# fightboard-tester.net
KiCad netlist of a schematic drawn in EAGLE
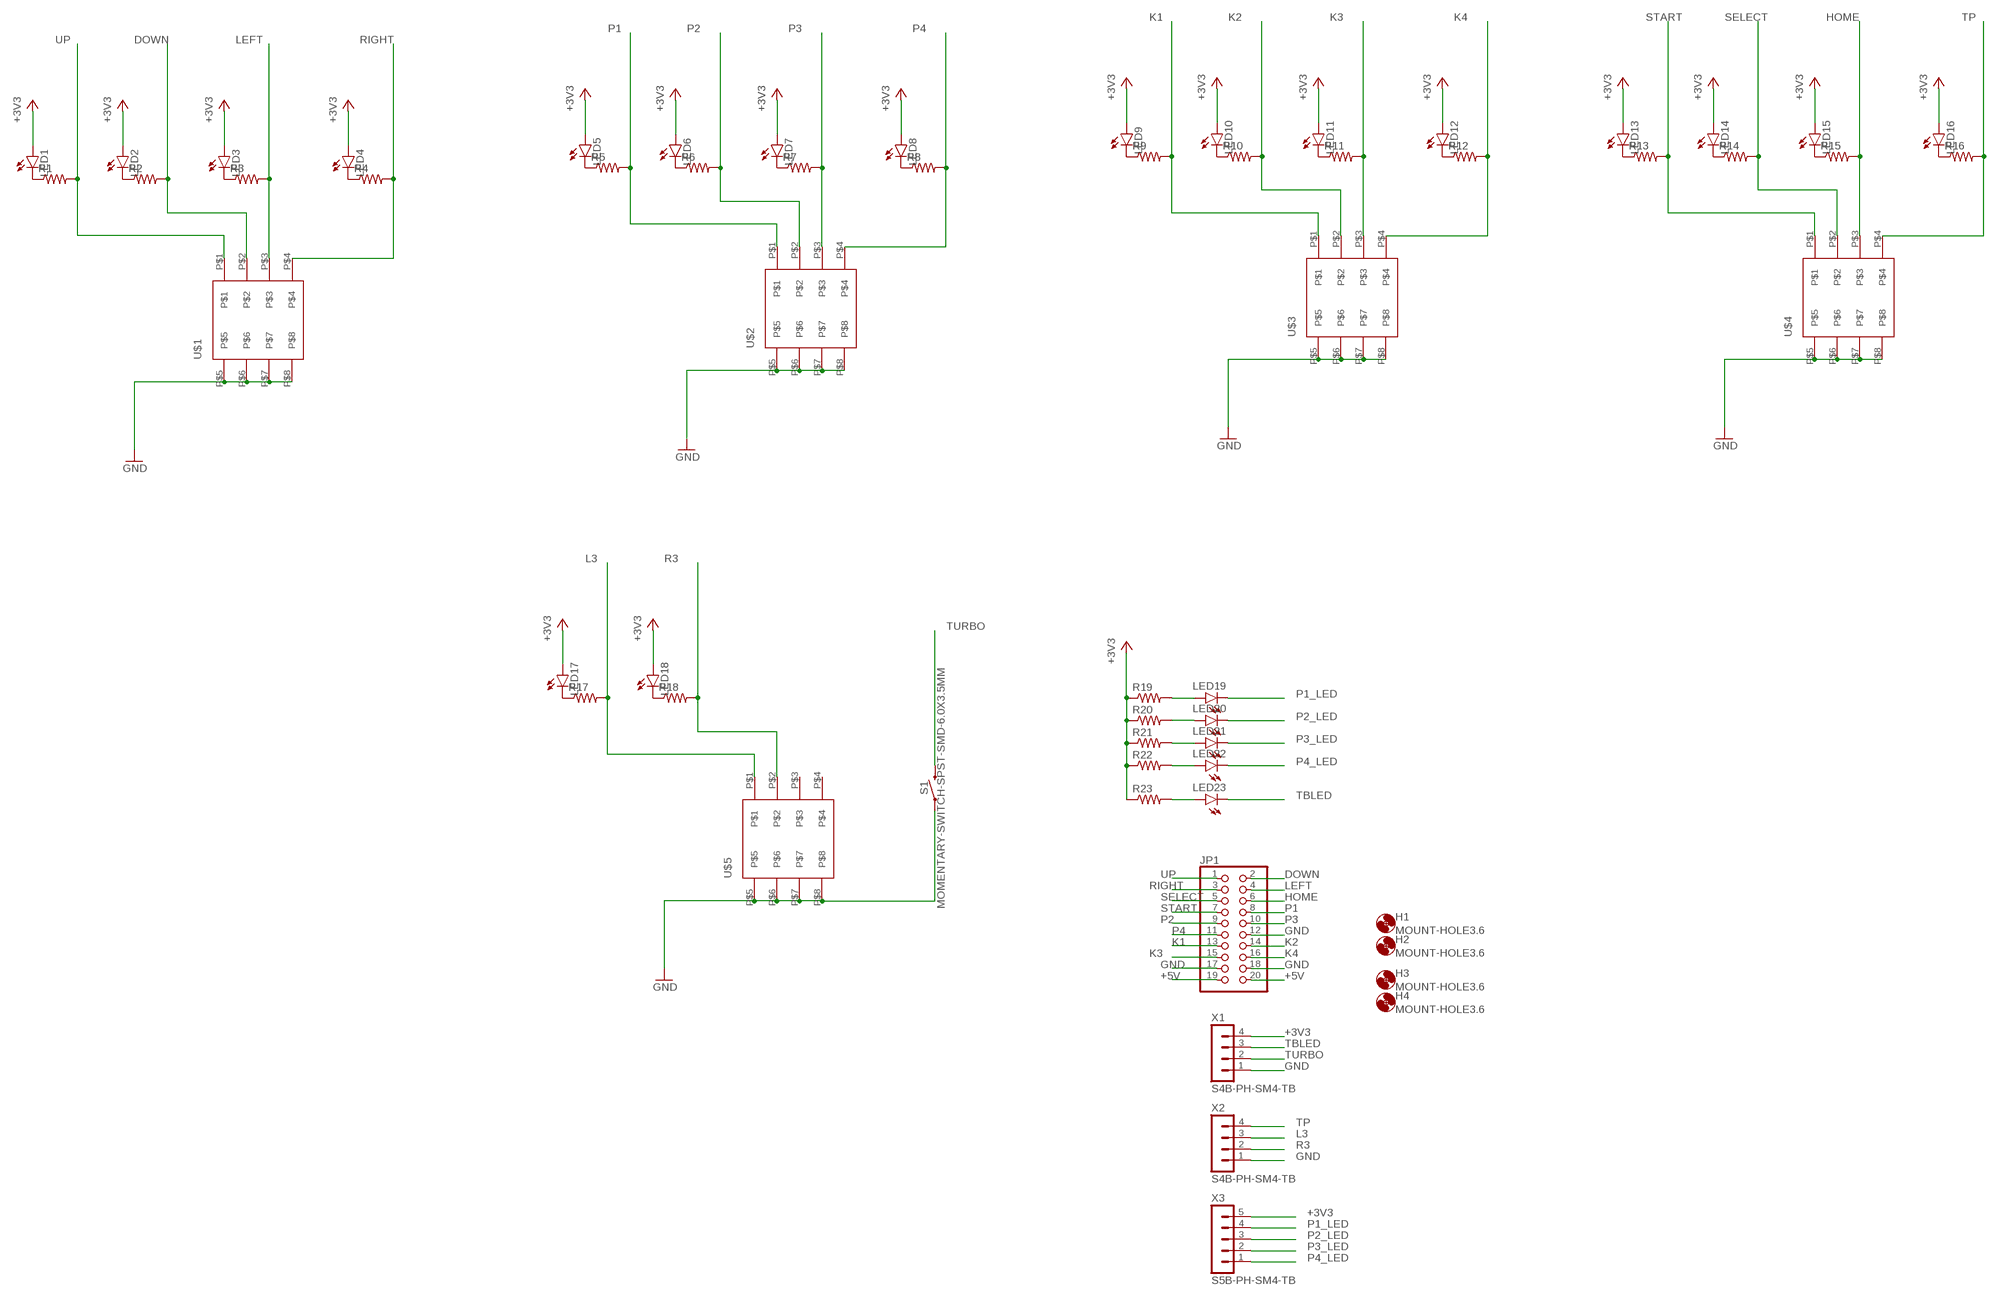
[diagram p0: schematic, sheet 1]

(export (version "E")
  (design (tool "Eeschema 10.0.6"))
  (components
    (comp (ref "H1")
      (value "MOUNT-HOLE3.6")
      (footprint "eagle-import:3,6")
      (libsource (lib "eagle-import") (part "MOUNT-HOLE3.6"))
    )
    (comp (ref "H2")
      (value "MOUNT-HOLE3.6")
      (footprint "eagle-import:3,6")
      (libsource (lib "eagle-import") (part "MOUNT-HOLE3.6"))
    )
    (comp (ref "H3")
      (value "MOUNT-HOLE3.6")
      (footprint "eagle-import:3,6")
      (libsource (lib "eagle-import") (part "MOUNT-HOLE3.6"))
    )
    (comp (ref "H4")
      (value "MOUNT-HOLE3.6")
      (footprint "eagle-import:3,6")
      (libsource (lib "eagle-import") (part "MOUNT-HOLE3.6"))
    )
    (comp (ref "JP1")
      (value "PINHD-2X10")
      (footprint "eagle-import:2X10")
      (libsource (lib "eagle-import") (part "PINHD-2X10"))
    )
    (comp (ref "LED1")
      (value "LEDCHIPLED_0805")
      (footprint "eagle-import:CHIPLED_0805")
      (libsource (lib "eagle-import") (part "LEDCHIPLED_0805"))
    )
    (comp (ref "LED2")
      (value "LEDCHIPLED_0805")
      (footprint "eagle-import:CHIPLED_0805")
      (libsource (lib "eagle-import") (part "LEDCHIPLED_0805"))
    )
    (comp (ref "LED3")
      (value "LEDCHIPLED_0805")
      (footprint "eagle-import:CHIPLED_0805")
      (libsource (lib "eagle-import") (part "LEDCHIPLED_0805"))
    )
    (comp (ref "LED4")
      (value "LEDCHIPLED_0805")
      (footprint "eagle-import:CHIPLED_0805")
      (libsource (lib "eagle-import") (part "LEDCHIPLED_0805"))
    )
    (comp (ref "LED5")
      (value "LEDCHIPLED_0805")
      (footprint "eagle-import:CHIPLED_0805")
      (libsource (lib "eagle-import") (part "LEDCHIPLED_0805"))
    )
    (comp (ref "LED6")
      (value "LEDCHIPLED_0805")
      (footprint "eagle-import:CHIPLED_0805")
      (libsource (lib "eagle-import") (part "LEDCHIPLED_0805"))
    )
    (comp (ref "LED7")
      (value "LEDCHIPLED_0805")
      (footprint "eagle-import:CHIPLED_0805")
      (libsource (lib "eagle-import") (part "LEDCHIPLED_0805"))
    )
    (comp (ref "LED8")
      (value "LEDCHIPLED_0805")
      (footprint "eagle-import:CHIPLED_0805")
      (libsource (lib "eagle-import") (part "LEDCHIPLED_0805"))
    )
    (comp (ref "LED9")
      (value "LEDCHIPLED_0805")
      (footprint "eagle-import:CHIPLED_0805")
      (libsource (lib "eagle-import") (part "LEDCHIPLED_0805"))
    )
    (comp (ref "LED10")
      (value "LEDCHIPLED_0805")
      (footprint "eagle-import:CHIPLED_0805")
      (libsource (lib "eagle-import") (part "LEDCHIPLED_0805"))
    )
    (comp (ref "LED11")
      (value "LEDCHIPLED_0805")
      (footprint "eagle-import:CHIPLED_0805")
      (libsource (lib "eagle-import") (part "LEDCHIPLED_0805"))
    )
    (comp (ref "LED12")
      (value "LEDCHIPLED_0805")
      (footprint "eagle-import:CHIPLED_0805")
      (libsource (lib "eagle-import") (part "LEDCHIPLED_0805"))
    )
    (comp (ref "LED13")
      (value "LEDCHIPLED_0805")
      (footprint "eagle-import:CHIPLED_0805")
      (libsource (lib "eagle-import") (part "LEDCHIPLED_0805"))
    )
    (comp (ref "LED14")
      (value "LEDCHIPLED_0805")
      (footprint "eagle-import:CHIPLED_0805")
      (libsource (lib "eagle-import") (part "LEDCHIPLED_0805"))
    )
    (comp (ref "LED15")
      (value "LEDCHIPLED_0805")
      (footprint "eagle-import:CHIPLED_0805")
      (libsource (lib "eagle-import") (part "LEDCHIPLED_0805"))
    )
    (comp (ref "LED16")
      (value "LEDCHIPLED_0805")
      (footprint "eagle-import:CHIPLED_0805")
      (libsource (lib "eagle-import") (part "LEDCHIPLED_0805"))
    )
    (comp (ref "LED17")
      (value "LEDCHIPLED_0805")
      (footprint "eagle-import:CHIPLED_0805")
      (libsource (lib "eagle-import") (part "LEDCHIPLED_0805"))
    )
    (comp (ref "LED18")
      (value "LEDCHIPLED_0805")
      (footprint "eagle-import:CHIPLED_0805")
      (libsource (lib "eagle-import") (part "LEDCHIPLED_0805"))
    )
    (comp (ref "LED19")
      (value "LEDCHIPLED_0805")
      (footprint "eagle-import:CHIPLED_0805")
      (libsource (lib "eagle-import") (part "LEDCHIPLED_0805"))
    )
    (comp (ref "LED20")
      (value "LEDCHIPLED_0805")
      (footprint "eagle-import:CHIPLED_0805")
      (libsource (lib "eagle-import") (part "LEDCHIPLED_0805"))
    )
    (comp (ref "LED21")
      (value "LEDCHIPLED_0805")
      (footprint "eagle-import:CHIPLED_0805")
      (libsource (lib "eagle-import") (part "LEDCHIPLED_0805"))
    )
    (comp (ref "LED22")
      (value "LEDCHIPLED_0805")
      (footprint "eagle-import:CHIPLED_0805")
      (libsource (lib "eagle-import") (part "LEDCHIPLED_0805"))
    )
    (comp (ref "LED23")
      (value "LEDCHIPLED_0805")
      (footprint "eagle-import:CHIPLED_0805")
      (libsource (lib "eagle-import") (part "LEDCHIPLED_0805"))
    )
    (comp (ref "R1")
      (value "R-US_R0805")
      (footprint "eagle-import:R0805")
      (libsource (lib "eagle-import") (part "R-US_R0805"))
    )
    (comp (ref "R2")
      (value "R-US_R0805")
      (footprint "eagle-import:R0805")
      (libsource (lib "eagle-import") (part "R-US_R0805"))
    )
    (comp (ref "R3")
      (value "R-US_R0805")
      (footprint "eagle-import:R0805")
      (libsource (lib "eagle-import") (part "R-US_R0805"))
    )
    (comp (ref "R4")
      (value "R-US_R0805")
      (footprint "eagle-import:R0805")
      (libsource (lib "eagle-import") (part "R-US_R0805"))
    )
    (comp (ref "R5")
      (value "R-US_R0805")
      (footprint "eagle-import:R0805")
      (libsource (lib "eagle-import") (part "R-US_R0805"))
    )
    (comp (ref "R6")
      (value "R-US_R0805")
      (footprint "eagle-import:R0805")
      (libsource (lib "eagle-import") (part "R-US_R0805"))
    )
    (comp (ref "R7")
      (value "R-US_R0805")
      (footprint "eagle-import:R0805")
      (libsource (lib "eagle-import") (part "R-US_R0805"))
    )
    (comp (ref "R8")
      (value "R-US_R0805")
      (footprint "eagle-import:R0805")
      (libsource (lib "eagle-import") (part "R-US_R0805"))
    )
    (comp (ref "R9")
      (value "R-US_R0805")
      (footprint "eagle-import:R0805")
      (libsource (lib "eagle-import") (part "R-US_R0805"))
    )
    (comp (ref "R10")
      (value "R-US_R0805")
      (footprint "eagle-import:R0805")
      (libsource (lib "eagle-import") (part "R-US_R0805"))
    )
    (comp (ref "R11")
      (value "R-US_R0805")
      (footprint "eagle-import:R0805")
      (libsource (lib "eagle-import") (part "R-US_R0805"))
    )
    (comp (ref "R12")
      (value "R-US_R0805")
      (footprint "eagle-import:R0805")
      (libsource (lib "eagle-import") (part "R-US_R0805"))
    )
    (comp (ref "R13")
      (value "R-US_R0805")
      (footprint "eagle-import:R0805")
      (libsource (lib "eagle-import") (part "R-US_R0805"))
    )
    (comp (ref "R14")
      (value "R-US_R0805")
      (footprint "eagle-import:R0805")
      (libsource (lib "eagle-import") (part "R-US_R0805"))
    )
    (comp (ref "R15")
      (value "R-US_R0805")
      (footprint "eagle-import:R0805")
      (libsource (lib "eagle-import") (part "R-US_R0805"))
    )
    (comp (ref "R16")
      (value "R-US_R0805")
      (footprint "eagle-import:R0805")
      (libsource (lib "eagle-import") (part "R-US_R0805"))
    )
    (comp (ref "R17")
      (value "R-US_R0805")
      (footprint "eagle-import:R0805")
      (libsource (lib "eagle-import") (part "R-US_R0805"))
    )
    (comp (ref "R18")
      (value "R-US_R0805")
      (footprint "eagle-import:R0805")
      (libsource (lib "eagle-import") (part "R-US_R0805"))
    )
    (comp (ref "R19")
      (value "R-US_R0805")
      (footprint "eagle-import:R0805")
      (libsource (lib "eagle-import") (part "R-US_R0805"))
    )
    (comp (ref "R20")
      (value "R-US_R0805")
      (footprint "eagle-import:R0805")
      (libsource (lib "eagle-import") (part "R-US_R0805"))
    )
    (comp (ref "R21")
      (value "R-US_R0805")
      (footprint "eagle-import:R0805")
      (libsource (lib "eagle-import") (part "R-US_R0805"))
    )
    (comp (ref "R22")
      (value "R-US_R0805")
      (footprint "eagle-import:R0805")
      (libsource (lib "eagle-import") (part "R-US_R0805"))
    )
    (comp (ref "R23")
      (value "R-US_R0805")
      (footprint "eagle-import:R0805")
      (libsource (lib "eagle-import") (part "R-US_R0805"))
    )
    (comp (ref "S1")
      (value "MOMENTARY-SWITCH-SPST-SMD-6.0X3.5MM")
      (footprint "eagle-import:TACTILE_SWITCH_SMD_6.0X3.5MM")
      (libsource (lib "eagle-import") (part "MOMENTARY-SWITCH-SPST-SMD-6.0X3.5MM"))
    )
    (comp (ref "U$1")
      (value "DSIC04LS")
      (footprint "eagle-import:DSIC04LS")
      (libsource (lib "eagle-import") (part "DSIC04LS"))
    )
    (comp (ref "U$2")
      (value "DSIC04LS")
      (footprint "eagle-import:DSIC04LS")
      (libsource (lib "eagle-import") (part "DSIC04LS"))
    )
    (comp (ref "U$3")
      (value "DSIC04LS")
      (footprint "eagle-import:DSIC04LS")
      (libsource (lib "eagle-import") (part "DSIC04LS"))
    )
    (comp (ref "U$4")
      (value "DSIC04LS")
      (footprint "eagle-import:DSIC04LS")
      (libsource (lib "eagle-import") (part "DSIC04LS"))
    )
    (comp (ref "U$5")
      (value "DSIC04LS")
      (footprint "eagle-import:DSIC04LS")
      (libsource (lib "eagle-import") (part "DSIC04LS"))
    )
    (comp (ref "X1")
      (value "S4B-PH-SM4-TB")
      (footprint "eagle-import:S4B-PH-SM4-TB")
      (libsource (lib "eagle-import") (part "S4B-PH-SM4-TB"))
    )
    (comp (ref "X2")
      (value "S4B-PH-SM4-TB")
      (footprint "eagle-import:S4B-PH-SM4-TB")
      (libsource (lib "eagle-import") (part "S4B-PH-SM4-TB"))
    )
    (comp (ref "X3")
      (value "S5B-PH-SM4-TB")
      (footprint "eagle-import:S5B-PH-SM4-TB")
      (libsource (lib "eagle-import") (part "S5B-PH-SM4-TB"))
    )
  )
  (nets
    (net (code "1") (name "+3V3") (class "Default")
      (node (ref "LED1") (pin "A") (pinfunction "A_A") (pintype "passive"))
      (node (ref "LED10") (pin "A") (pinfunction "A_A") (pintype "passive"))
      (node (ref "LED11") (pin "A") (pinfunction "A_A") (pintype "passive"))
      (node (ref "LED12") (pin "A") (pinfunction "A_A") (pintype "passive"))
      (node (ref "LED13") (pin "A") (pinfunction "A_A") (pintype "passive"))
      (node (ref "LED14") (pin "A") (pinfunction "A_A") (pintype "passive"))
      (node (ref "LED15") (pin "A") (pinfunction "A_A") (pintype "passive"))
      (node (ref "LED16") (pin "A") (pinfunction "A_A") (pintype "passive"))
      (node (ref "LED17") (pin "A") (pinfunction "A_A") (pintype "passive"))
      (node (ref "LED18") (pin "A") (pinfunction "A_A") (pintype "passive"))
      (node (ref "LED2") (pin "A") (pinfunction "A_A") (pintype "passive"))
      (node (ref "LED3") (pin "A") (pinfunction "A_A") (pintype "passive"))
      (node (ref "LED4") (pin "A") (pinfunction "A_A") (pintype "passive"))
      (node (ref "LED5") (pin "A") (pinfunction "A_A") (pintype "passive"))
      (node (ref "LED6") (pin "A") (pinfunction "A_A") (pintype "passive"))
      (node (ref "LED7") (pin "A") (pinfunction "A_A") (pintype "passive"))
      (node (ref "LED8") (pin "A") (pinfunction "A_A") (pintype "passive"))
      (node (ref "LED9") (pin "A") (pinfunction "A_A") (pintype "passive"))
      (node (ref "R19") (pin "1") (pinfunction "1_1") (pintype "passive"))
      (node (ref "R20") (pin "1") (pinfunction "1_1") (pintype "passive"))
      (node (ref "R21") (pin "1") (pinfunction "1_1") (pintype "passive"))
      (node (ref "R22") (pin "1") (pinfunction "1_1") (pintype "passive"))
      (node (ref "R23") (pin "1") (pinfunction "1_1") (pintype "passive"))
      (node (ref "X1") (pin "4") (pinfunction "4_4") (pintype "passive"))
      (node (ref "X3") (pin "5") (pinfunction "5_5") (pintype "passive"))
    )
    (net (code "2") (name "/+5V") (class "Default")
      (node (ref "JP1") (pin "19") (pinfunction "19_19") (pintype "passive"))
      (node (ref "JP1") (pin "20") (pinfunction "20_20") (pintype "passive"))
    )
    (net (code "3") (name "/DOWN") (class "Default")
      (node (ref "JP1") (pin "2") (pinfunction "2_2") (pintype "passive"))
      (node (ref "R2") (pin "2") (pinfunction "2_2") (pintype "passive"))
      (node (ref "U$1") (pin "P$2") (pinfunction "P$2_P$2") (pintype "bidirectional"))
    )
    (net (code "4") (name "/HOME") (class "Default")
      (node (ref "JP1") (pin "6") (pinfunction "6_6") (pintype "passive"))
      (node (ref "R15") (pin "2") (pinfunction "2_2") (pintype "passive"))
      (node (ref "U$4") (pin "P$3") (pinfunction "P$3_P$3") (pintype "bidirectional"))
    )
    (net (code "5") (name "/K1") (class "Default")
      (node (ref "JP1") (pin "13") (pinfunction "13_13") (pintype "passive"))
      (node (ref "R9") (pin "2") (pinfunction "2_2") (pintype "passive"))
      (node (ref "U$3") (pin "P$1") (pinfunction "P$1_P$1") (pintype "bidirectional"))
    )
    (net (code "6") (name "/K2") (class "Default")
      (node (ref "JP1") (pin "14") (pinfunction "14_14") (pintype "passive"))
      (node (ref "R10") (pin "2") (pinfunction "2_2") (pintype "passive"))
      (node (ref "U$3") (pin "P$2") (pinfunction "P$2_P$2") (pintype "bidirectional"))
    )
    (net (code "7") (name "/K3") (class "Default")
      (node (ref "JP1") (pin "15") (pinfunction "15_15") (pintype "passive"))
      (node (ref "R11") (pin "2") (pinfunction "2_2") (pintype "passive"))
      (node (ref "U$3") (pin "P$3") (pinfunction "P$3_P$3") (pintype "bidirectional"))
    )
    (net (code "8") (name "/K4") (class "Default")
      (node (ref "JP1") (pin "16") (pinfunction "16_16") (pintype "passive"))
      (node (ref "R12") (pin "2") (pinfunction "2_2") (pintype "passive"))
      (node (ref "U$3") (pin "P$4") (pinfunction "P$4_P$4") (pintype "bidirectional"))
    )
    (net (code "9") (name "/L3") (class "Default")
      (node (ref "R17") (pin "2") (pinfunction "2_2") (pintype "passive"))
      (node (ref "U$5") (pin "P$1") (pinfunction "P$1_P$1") (pintype "bidirectional"))
      (node (ref "X2") (pin "3") (pinfunction "3_3") (pintype "passive"))
    )
    (net (code "10") (name "/LEFT") (class "Default")
      (node (ref "JP1") (pin "4") (pinfunction "4_4") (pintype "passive"))
      (node (ref "R3") (pin "2") (pinfunction "2_2") (pintype "passive"))
      (node (ref "U$1") (pin "P$3") (pinfunction "P$3_P$3") (pintype "bidirectional"))
    )
    (net (code "11") (name "/P1") (class "Default")
      (node (ref "JP1") (pin "8") (pinfunction "8_8") (pintype "passive"))
      (node (ref "R5") (pin "2") (pinfunction "2_2") (pintype "passive"))
      (node (ref "U$2") (pin "P$1") (pinfunction "P$1_P$1") (pintype "bidirectional"))
    )
    (net (code "12") (name "/P1_LED") (class "Default")
      (node (ref "LED19") (pin "C") (pinfunction "C_C") (pintype "passive"))
      (node (ref "X3") (pin "4") (pinfunction "4_4") (pintype "passive"))
    )
    (net (code "13") (name "/P2") (class "Default")
      (node (ref "JP1") (pin "9") (pinfunction "9_9") (pintype "passive"))
      (node (ref "R6") (pin "2") (pinfunction "2_2") (pintype "passive"))
      (node (ref "U$2") (pin "P$2") (pinfunction "P$2_P$2") (pintype "bidirectional"))
    )
    (net (code "14") (name "/P2_LED") (class "Default")
      (node (ref "LED20") (pin "C") (pinfunction "C_C") (pintype "passive"))
      (node (ref "X3") (pin "3") (pinfunction "3_3") (pintype "passive"))
    )
    (net (code "15") (name "/P3") (class "Default")
      (node (ref "JP1") (pin "10") (pinfunction "10_10") (pintype "passive"))
      (node (ref "R7") (pin "2") (pinfunction "2_2") (pintype "passive"))
      (node (ref "U$2") (pin "P$3") (pinfunction "P$3_P$3") (pintype "bidirectional"))
    )
    (net (code "16") (name "/P3_LED") (class "Default")
      (node (ref "LED21") (pin "C") (pinfunction "C_C") (pintype "passive"))
      (node (ref "X3") (pin "2") (pinfunction "2_2") (pintype "passive"))
    )
    (net (code "17") (name "/P4") (class "Default")
      (node (ref "JP1") (pin "11") (pinfunction "11_11") (pintype "passive"))
      (node (ref "R8") (pin "2") (pinfunction "2_2") (pintype "passive"))
      (node (ref "U$2") (pin "P$4") (pinfunction "P$4_P$4") (pintype "bidirectional"))
    )
    (net (code "18") (name "/P4_LED") (class "Default")
      (node (ref "LED22") (pin "C") (pinfunction "C_C") (pintype "passive"))
      (node (ref "X3") (pin "1") (pinfunction "1_1") (pintype "passive"))
    )
    (net (code "19") (name "/R3") (class "Default")
      (node (ref "R18") (pin "2") (pinfunction "2_2") (pintype "passive"))
      (node (ref "U$5") (pin "P$2") (pinfunction "P$2_P$2") (pintype "bidirectional"))
      (node (ref "X2") (pin "2") (pinfunction "2_2") (pintype "passive"))
    )
    (net (code "20") (name "/RIGHT") (class "Default")
      (node (ref "JP1") (pin "3") (pinfunction "3_3") (pintype "passive"))
      (node (ref "R4") (pin "2") (pinfunction "2_2") (pintype "passive"))
      (node (ref "U$1") (pin "P$4") (pinfunction "P$4_P$4") (pintype "bidirectional"))
    )
    (net (code "21") (name "/SELECT") (class "Default")
      (node (ref "JP1") (pin "5") (pinfunction "5_5") (pintype "passive"))
      (node (ref "R14") (pin "2") (pinfunction "2_2") (pintype "passive"))
      (node (ref "U$4") (pin "P$2") (pinfunction "P$2_P$2") (pintype "bidirectional"))
    )
    (net (code "22") (name "/START") (class "Default")
      (node (ref "JP1") (pin "7") (pinfunction "7_7") (pintype "passive"))
      (node (ref "R13") (pin "2") (pinfunction "2_2") (pintype "passive"))
      (node (ref "U$4") (pin "P$1") (pinfunction "P$1_P$1") (pintype "bidirectional"))
    )
    (net (code "23") (name "/TBLED") (class "Default")
      (node (ref "LED23") (pin "C") (pinfunction "C_C") (pintype "passive"))
      (node (ref "X1") (pin "3") (pinfunction "3_3") (pintype "passive"))
    )
    (net (code "24") (name "/TP") (class "Default")
      (node (ref "R16") (pin "2") (pinfunction "2_2") (pintype "passive"))
      (node (ref "U$4") (pin "P$4") (pinfunction "P$4_P$4") (pintype "bidirectional"))
      (node (ref "X2") (pin "4") (pinfunction "4_4") (pintype "passive"))
    )
    (net (code "25") (name "/TURBO") (class "Default")
      (node (ref "S1") (pin "2") (pinfunction "2_2") (pintype "passive"))
      (node (ref "X1") (pin "2") (pinfunction "2_2") (pintype "passive"))
    )
    (net (code "26") (name "/UP") (class "Default")
      (node (ref "JP1") (pin "1") (pinfunction "1_1") (pintype "passive"))
      (node (ref "R1") (pin "2") (pinfunction "2_2") (pintype "passive"))
      (node (ref "U$1") (pin "P$1") (pinfunction "P$1_P$1") (pintype "bidirectional"))
    )
    (net (code "27") (name "GND") (class "Default")
      (node (ref "JP1") (pin "12") (pinfunction "12_12") (pintype "passive"))
      (node (ref "JP1") (pin "17") (pinfunction "17_17") (pintype "passive"))
      (node (ref "JP1") (pin "18") (pinfunction "18_18") (pintype "passive"))
      (node (ref "S1") (pin "1") (pinfunction "1_1") (pintype "passive"))
      (node (ref "U$1") (pin "P$5") (pinfunction "P$5_P$5") (pintype "bidirectional"))
      (node (ref "U$1") (pin "P$6") (pinfunction "P$6_P$6") (pintype "bidirectional"))
      (node (ref "U$1") (pin "P$7") (pinfunction "P$7_P$7") (pintype "bidirectional"))
      (node (ref "U$1") (pin "P$8") (pinfunction "P$8_P$8") (pintype "bidirectional"))
      (node (ref "U$2") (pin "P$5") (pinfunction "P$5_P$5") (pintype "bidirectional"))
      (node (ref "U$2") (pin "P$6") (pinfunction "P$6_P$6") (pintype "bidirectional"))
      (node (ref "U$2") (pin "P$7") (pinfunction "P$7_P$7") (pintype "bidirectional"))
      (node (ref "U$2") (pin "P$8") (pinfunction "P$8_P$8") (pintype "bidirectional"))
      (node (ref "U$3") (pin "P$5") (pinfunction "P$5_P$5") (pintype "bidirectional"))
      (node (ref "U$3") (pin "P$6") (pinfunction "P$6_P$6") (pintype "bidirectional"))
      (node (ref "U$3") (pin "P$7") (pinfunction "P$7_P$7") (pintype "bidirectional"))
      (node (ref "U$3") (pin "P$8") (pinfunction "P$8_P$8") (pintype "bidirectional"))
      (node (ref "U$4") (pin "P$5") (pinfunction "P$5_P$5") (pintype "bidirectional"))
      (node (ref "U$4") (pin "P$6") (pinfunction "P$6_P$6") (pintype "bidirectional"))
      (node (ref "U$4") (pin "P$7") (pinfunction "P$7_P$7") (pintype "bidirectional"))
      (node (ref "U$4") (pin "P$8") (pinfunction "P$8_P$8") (pintype "bidirectional"))
      (node (ref "U$5") (pin "P$5") (pinfunction "P$5_P$5") (pintype "bidirectional"))
      (node (ref "U$5") (pin "P$6") (pinfunction "P$6_P$6") (pintype "bidirectional"))
      (node (ref "U$5") (pin "P$7") (pinfunction "P$7_P$7") (pintype "bidirectional"))
      (node (ref "U$5") (pin "P$8") (pinfunction "P$8_P$8") (pintype "bidirectional"))
      (node (ref "X1") (pin "1") (pinfunction "1_1") (pintype "passive"))
      (node (ref "X2") (pin "1") (pinfunction "1_1") (pintype "passive"))
    )
    (net (code "28") (name "Net-(LED1-PadC)") (class "Default")
      (node (ref "LED1") (pin "C") (pinfunction "C_C") (pintype "passive"))
      (node (ref "R1") (pin "1") (pinfunction "1_1") (pintype "passive"))
    )
    (net (code "29") (name "Net-(LED2-PadC)") (class "Default")
      (node (ref "LED2") (pin "C") (pinfunction "C_C") (pintype "passive"))
      (node (ref "R2") (pin "1") (pinfunction "1_1") (pintype "passive"))
    )
    (net (code "30") (name "Net-(LED3-PadC)") (class "Default")
      (node (ref "LED3") (pin "C") (pinfunction "C_C") (pintype "passive"))
      (node (ref "R3") (pin "1") (pinfunction "1_1") (pintype "passive"))
    )
    (net (code "31") (name "Net-(LED4-PadC)") (class "Default")
      (node (ref "LED4") (pin "C") (pinfunction "C_C") (pintype "passive"))
      (node (ref "R4") (pin "1") (pinfunction "1_1") (pintype "passive"))
    )
    (net (code "32") (name "Net-(LED5-PadC)") (class "Default")
      (node (ref "LED5") (pin "C") (pinfunction "C_C") (pintype "passive"))
      (node (ref "R5") (pin "1") (pinfunction "1_1") (pintype "passive"))
    )
    (net (code "33") (name "Net-(LED6-PadC)") (class "Default")
      (node (ref "LED6") (pin "C") (pinfunction "C_C") (pintype "passive"))
      (node (ref "R6") (pin "1") (pinfunction "1_1") (pintype "passive"))
    )
    (net (code "34") (name "Net-(LED7-PadC)") (class "Default")
      (node (ref "LED7") (pin "C") (pinfunction "C_C") (pintype "passive"))
      (node (ref "R7") (pin "1") (pinfunction "1_1") (pintype "passive"))
    )
    (net (code "35") (name "Net-(LED8-PadC)") (class "Default")
      (node (ref "LED8") (pin "C") (pinfunction "C_C") (pintype "passive"))
      (node (ref "R8") (pin "1") (pinfunction "1_1") (pintype "passive"))
    )
    (net (code "36") (name "Net-(LED9-PadC)") (class "Default")
      (node (ref "LED9") (pin "C") (pinfunction "C_C") (pintype "passive"))
      (node (ref "R9") (pin "1") (pinfunction "1_1") (pintype "passive"))
    )
    (net (code "37") (name "Net-(LED10-PadC)") (class "Default")
      (node (ref "LED10") (pin "C") (pinfunction "C_C") (pintype "passive"))
      (node (ref "R10") (pin "1") (pinfunction "1_1") (pintype "passive"))
    )
    (net (code "38") (name "Net-(LED11-PadC)") (class "Default")
      (node (ref "LED11") (pin "C") (pinfunction "C_C") (pintype "passive"))
      (node (ref "R11") (pin "1") (pinfunction "1_1") (pintype "passive"))
    )
    (net (code "39") (name "Net-(LED12-PadC)") (class "Default")
      (node (ref "LED12") (pin "C") (pinfunction "C_C") (pintype "passive"))
      (node (ref "R12") (pin "1") (pinfunction "1_1") (pintype "passive"))
    )
    (net (code "40") (name "Net-(LED13-PadC)") (class "Default")
      (node (ref "LED13") (pin "C") (pinfunction "C_C") (pintype "passive"))
      (node (ref "R13") (pin "1") (pinfunction "1_1") (pintype "passive"))
    )
    (net (code "41") (name "Net-(LED14-PadC)") (class "Default")
      (node (ref "LED14") (pin "C") (pinfunction "C_C") (pintype "passive"))
      (node (ref "R14") (pin "1") (pinfunction "1_1") (pintype "passive"))
    )
    (net (code "42") (name "Net-(LED15-PadC)") (class "Default")
      (node (ref "LED15") (pin "C") (pinfunction "C_C") (pintype "passive"))
      (node (ref "R15") (pin "1") (pinfunction "1_1") (pintype "passive"))
    )
    (net (code "43") (name "Net-(LED16-PadC)") (class "Default")
      (node (ref "LED16") (pin "C") (pinfunction "C_C") (pintype "passive"))
      (node (ref "R16") (pin "1") (pinfunction "1_1") (pintype "passive"))
    )
    (net (code "44") (name "Net-(LED17-PadC)") (class "Default")
      (node (ref "LED17") (pin "C") (pinfunction "C_C") (pintype "passive"))
      (node (ref "R17") (pin "1") (pinfunction "1_1") (pintype "passive"))
    )
    (net (code "45") (name "Net-(LED18-PadC)") (class "Default")
      (node (ref "LED18") (pin "C") (pinfunction "C_C") (pintype "passive"))
      (node (ref "R18") (pin "1") (pinfunction "1_1") (pintype "passive"))
    )
    (net (code "46") (name "Net-(LED19-PadA)") (class "Default")
      (node (ref "LED19") (pin "A") (pinfunction "A_A") (pintype "passive"))
      (node (ref "R19") (pin "2") (pinfunction "2_2") (pintype "passive"))
    )
    (net (code "47") (name "Net-(LED20-PadA)") (class "Default")
      (node (ref "LED20") (pin "A") (pinfunction "A_A") (pintype "passive"))
      (node (ref "R20") (pin "2") (pinfunction "2_2") (pintype "passive"))
    )
    (net (code "48") (name "Net-(LED21-PadA)") (class "Default")
      (node (ref "LED21") (pin "A") (pinfunction "A_A") (pintype "passive"))
      (node (ref "R21") (pin "2") (pinfunction "2_2") (pintype "passive"))
    )
    (net (code "49") (name "Net-(LED22-PadA)") (class "Default")
      (node (ref "LED22") (pin "A") (pinfunction "A_A") (pintype "passive"))
      (node (ref "R22") (pin "2") (pinfunction "2_2") (pintype "passive"))
    )
    (net (code "50") (name "Net-(LED23-PadA)") (class "Default")
      (node (ref "LED23") (pin "A") (pinfunction "A_A") (pintype "passive"))
      (node (ref "R23") (pin "2") (pinfunction "2_2") (pintype "passive"))
    )
    (net (code "51") (name "unconnected-(U$5-PadP$3)") (class "Default")
      (node (ref "U$5") (pin "P$3") (pinfunction "P$3_P$3") (pintype "bidirectional"))
    )
    (net (code "52") (name "unconnected-(U$5-PadP$4)") (class "Default")
      (node (ref "U$5") (pin "P$4") (pinfunction "P$4_P$4") (pintype "bidirectional"))
    )
  )
)
